# 1-Schematic_project_BIMO.net
KiCad netlist of a schematic drawn in EasyEDA
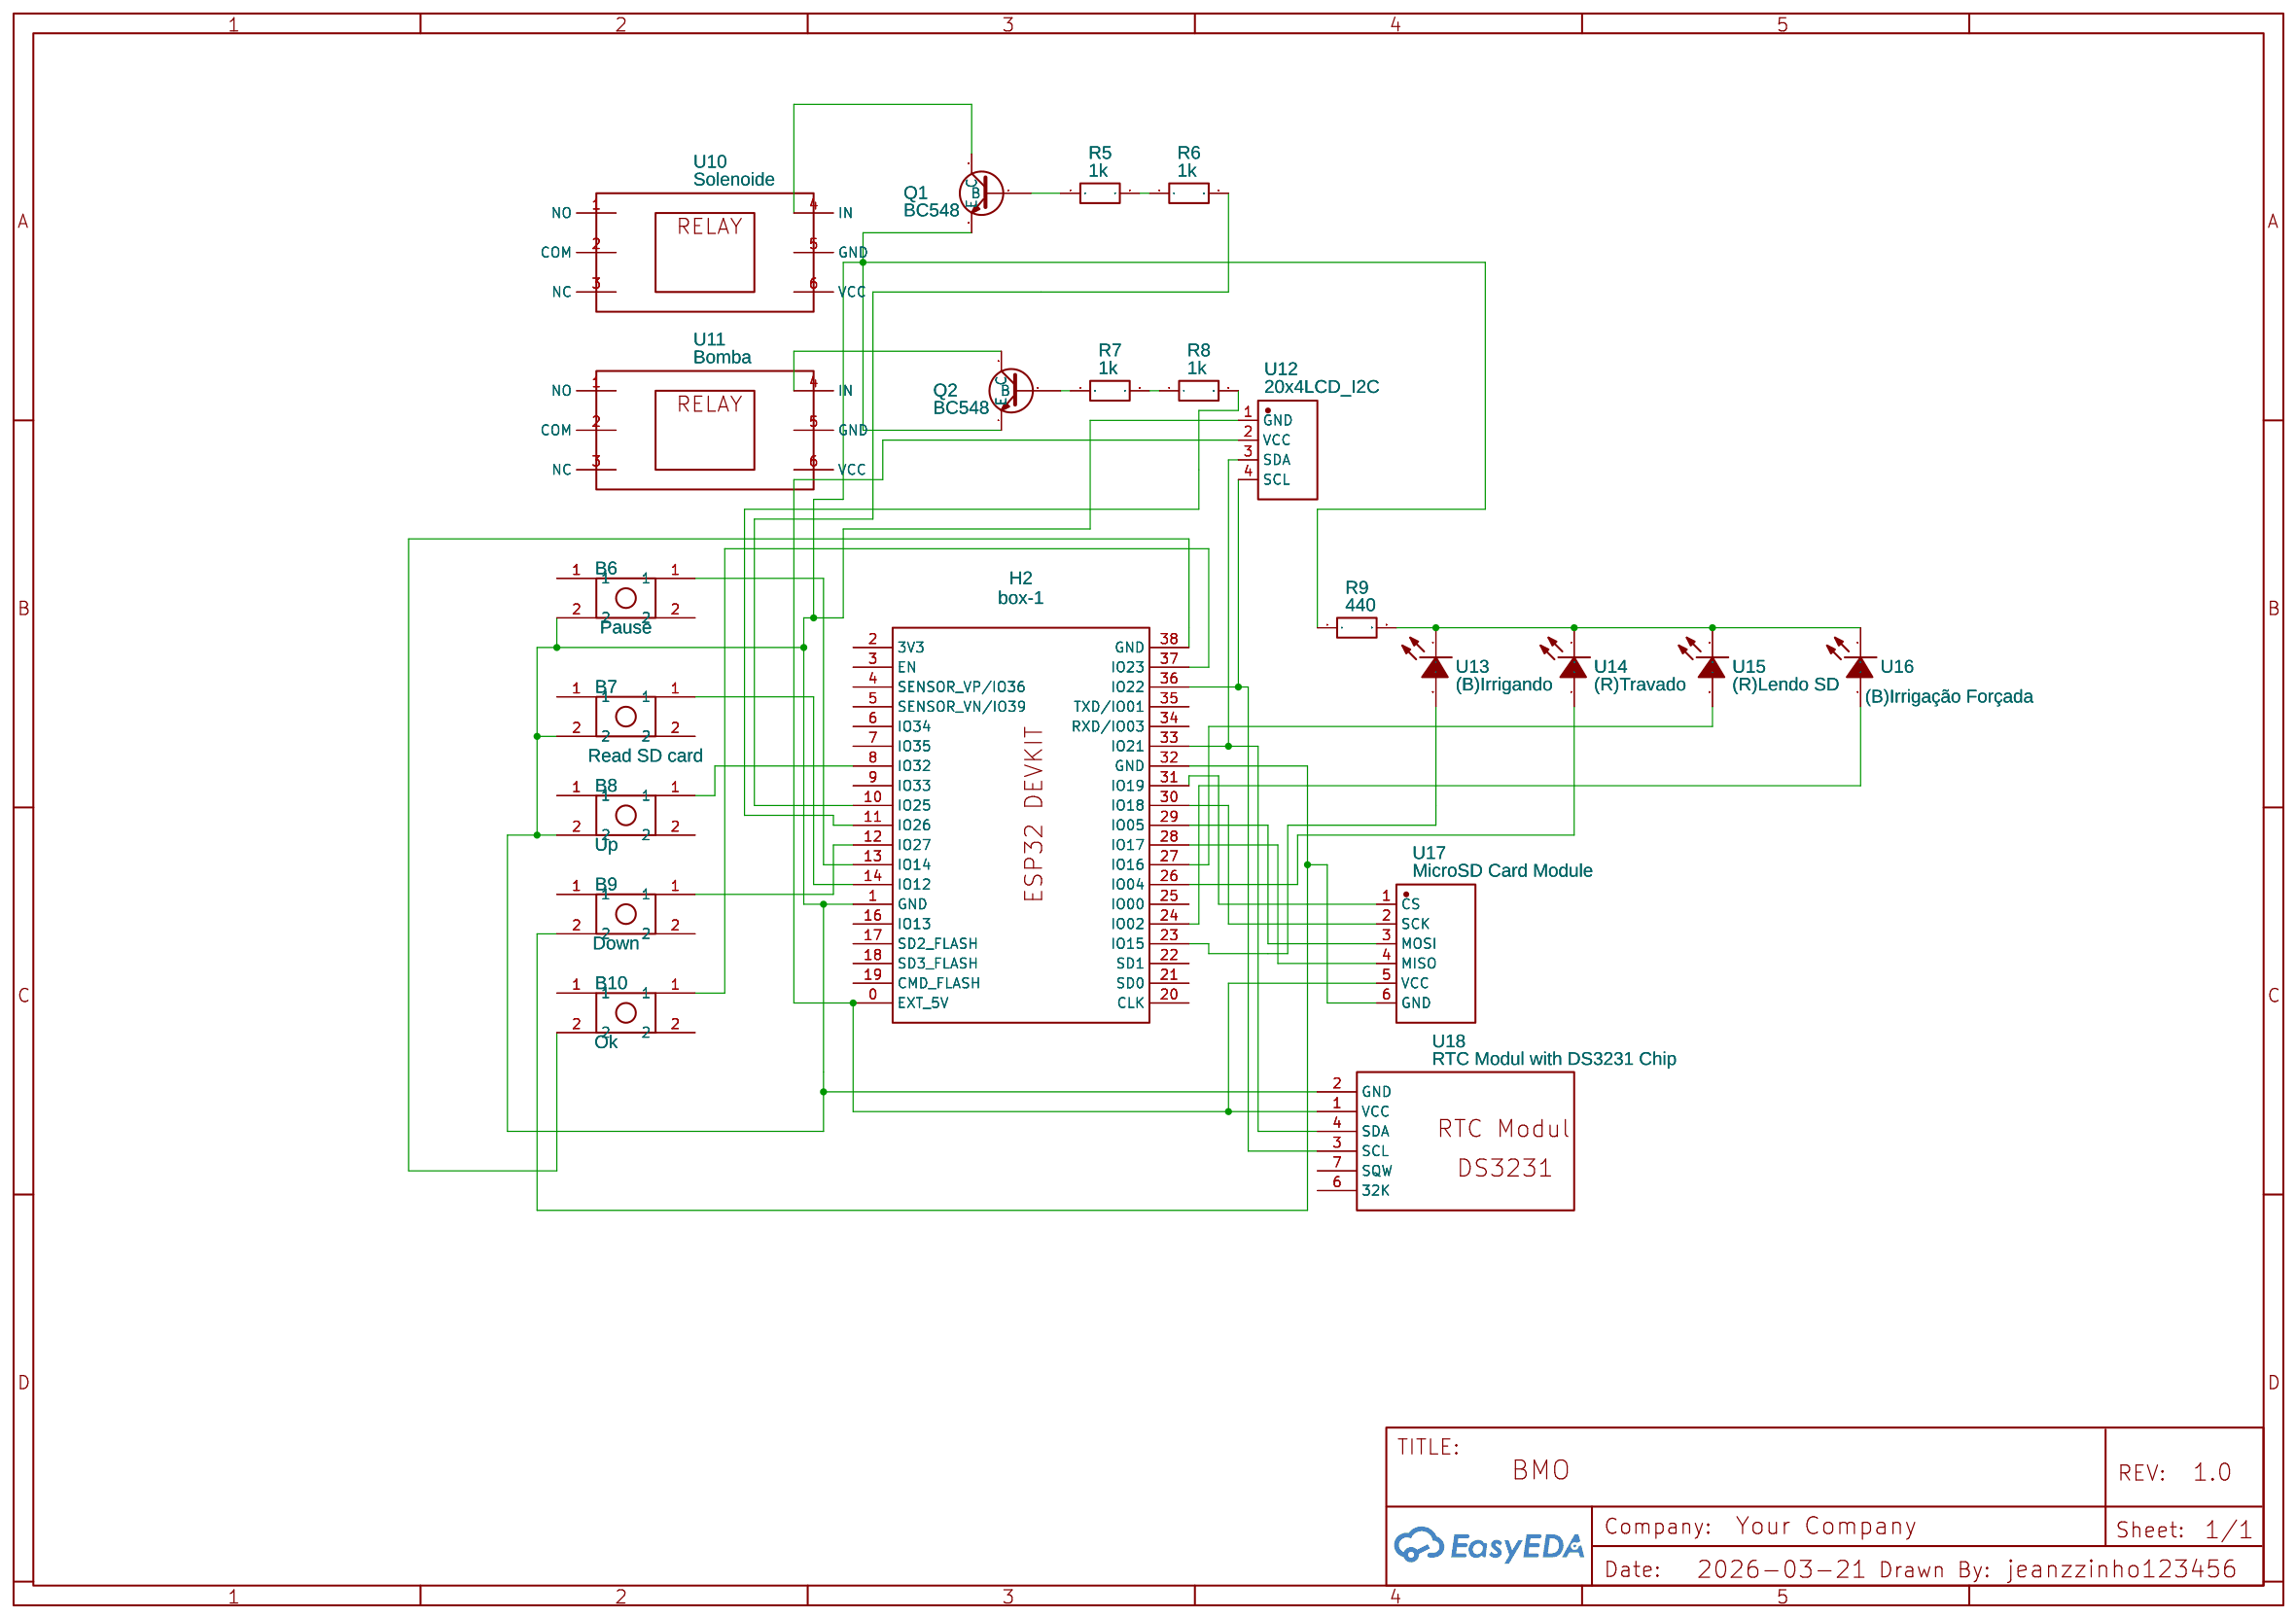
[diagram p0: schematic sheet]

(export (version "E")
  (design (tool "Eeschema 10.0.6"))
  (components
    (comp (ref "B6") (value "Pause") (libsource (lib "") (part "Push-buttom smd 6x6")))
    (comp (ref "B7") (value "Read SD card") (libsource (lib "") (part "Push-buttom smd 6x6")))
    (comp (ref "B8") (value "Up") (libsource (lib "") (part "Push-buttom smd 6x6")))
    (comp (ref "B9") (value "Down") (libsource (lib "") (part "Push-buttom smd 6x6")))
    (comp (ref "B10") (value "Ok") (libsource (lib "") (part "Push-buttom smd 6x6")))
    (comp (ref "H2")
      (value "box-1")
      (fields
        (field (name "Manufacturer Part") "2.54mm 1*19P Female header")
        (field (name "Manufacturer") "BOOMELE")
      )
      (libsource (lib "") (part "box-1"))
    )
    (comp (ref "Q1") (value "BC548") (libsource (lib "") (part "TRANSISTOR NPN CBE")))
    (comp (ref "Q2") (value "BC548") (libsource (lib "") (part "TRANSISTOR NPN CBE")))
    (comp (ref "R5") (value "1k") (libsource (lib "") (part "R_0603_EU")))
    (comp (ref "R6") (value "1k") (libsource (lib "") (part "R_0603_EU")))
    (comp (ref "R7") (value "1k") (libsource (lib "") (part "R_0603_EU")))
    (comp (ref "R8") (value "1k") (libsource (lib "") (part "R_0603_EU")))
    (comp (ref "R9") (value "440") (libsource (lib "") (part "R_0603_EU")))
    (comp (ref "U10") (value "Solenoide") (libsource (lib "") (part "1 CHANNEL RELAY MODULE")))
    (comp (ref "U11") (value "Bomba") (libsource (lib "") (part "1 CHANNEL RELAY MODULE")))
    (comp (ref "U12") (value "20x4LCD_I2C") (libsource (lib "") (part "20x4LCD_I2C")))
    (comp (ref "U13")
      (value "(B)Irrigando")
      (fields (field (name "Manufacturer Part") "720-LCGH9RNMXNX1"))
      (libsource (lib "") (part "720-LCGH9RNMXNX1"))
    )
    (comp (ref "U14")
      (value "(R)Travado")
      (fields (field (name "Manufacturer Part") "720-LCGH9RNMXNX1"))
      (libsource (lib "") (part "720-LCGH9RNMXNX1"))
    )
    (comp (ref "U15")
      (value "(R)Lendo SD")
      (fields (field (name "Manufacturer Part") "720-LCGH9RNMXNX1"))
      (libsource (lib "") (part "720-LCGH9RNMXNX1"))
    )
    (comp (ref "U16")
      (value "(B)Irrigação Forçada")
      (fields (field (name "Manufacturer Part") "720-LCGH9RNMXNX1"))
      (libsource (lib "") (part "720-LCGH9RNMXNX1"))
    )
    (comp (ref "U17") (value "MicroSD Card Module") (libsource (lib "") (part "MicroSD Card Module")))
    (comp (ref "U18")
      (value "RTC Modul with DS3231 Chip")
      (libsource (lib "") (part "RTC Modul with DS3231 Chip"))
    )
  )
  (nets
    (net (code "1") (name "Net-(B10-Pad2)_1") (class "Default")
      (node (ref "B10") (pin "2") (pinfunction "2_2") (pintype "input"))
      (node (ref "H2") (pin "38") (pinfunction "GND_38") (pintype "passive"))
    )
    (net (code "2") (name "Net-(H2-EXT_5V)") (class "Default")
      (node (ref "H2") (pin "0") (pinfunction "EXT_5V_0") (pintype "passive"))
      (node (ref "U12") (pin "2") (pinfunction "VCC_2") (pintype "unspecified"))
      (node (ref "U17") (pin "5") (pinfunction "VCC_5") (pintype "unspecified"))
      (node (ref "U18") (pin "1") (pinfunction "VCC_1") (pintype "unspecified"))
    )
    (net (code "3") (name "Net-(H2-IO02)") (class "Default")
      (node (ref "H2") (pin "23") (pinfunction "IO15_23") (pintype "bidirectional"))
      (node (ref "H2") (pin "24") (pinfunction "IO02_24") (pintype "bidirectional"))
      (node (ref "U13") (pin "2") (pinfunction "A_2") (pintype "unspecified"))
      (node (ref "U16") (pin "2") (pinfunction "A_2") (pintype "unspecified"))
    )
    (net (code "4") (name "Net-(H2-IO04)") (class "Default")
      (node (ref "H2") (pin "26") (pinfunction "IO04_26") (pintype "bidirectional"))
      (node (ref "U14") (pin "2") (pinfunction "A_2") (pintype "unspecified"))
    )
    (net (code "5") (name "Net-(H2-IO05)") (class "Default")
      (node (ref "H2") (pin "29") (pinfunction "IO05_29") (pintype "bidirectional"))
      (node (ref "U17") (pin "3") (pinfunction "MOSI_3") (pintype "unspecified"))
    )
    (net (code "6") (name "Net-(H2-IO12)") (class "Default")
      (node (ref "B7") (pin "1") (pinfunction "1_1") (pintype "output"))
      (node (ref "H2") (pin "14") (pinfunction "IO12_14") (pintype "bidirectional"))
    )
    (net (code "7") (name "Net-(H2-IO14)") (class "Default")
      (node (ref "B6") (pin "1") (pinfunction "1_1") (pintype "output"))
      (node (ref "H2") (pin "13") (pinfunction "IO14_13") (pintype "bidirectional"))
    )
    (net (code "8") (name "Net-(H2-IO16)") (class "Default")
      (node (ref "H2") (pin "27") (pinfunction "IO16_27") (pintype "bidirectional"))
      (node (ref "U15") (pin "2") (pinfunction "A_2") (pintype "unspecified"))
    )
    (net (code "9") (name "Net-(H2-IO17)") (class "Default")
      (node (ref "H2") (pin "28") (pinfunction "IO17_28") (pintype "bidirectional"))
      (node (ref "U17") (pin "4") (pinfunction "MISO_4") (pintype "unspecified"))
    )
    (net (code "10") (name "Net-(H2-IO18)") (class "Default")
      (node (ref "H2") (pin "30") (pinfunction "IO18_30") (pintype "bidirectional"))
      (node (ref "U17") (pin "2") (pinfunction "SCK_2") (pintype "unspecified"))
    )
    (net (code "11") (name "Net-(H2-IO19)") (class "Default")
      (node (ref "H2") (pin "31") (pinfunction "IO19_31") (pintype "bidirectional"))
      (node (ref "U17") (pin "1") (pinfunction "CS_1") (pintype "unspecified"))
    )
    (net (code "12") (name "Net-(H2-IO21)") (class "Default")
      (node (ref "H2") (pin "33") (pinfunction "IO21_33") (pintype "bidirectional"))
      (node (ref "U12") (pin "3") (pinfunction "SDA_3") (pintype "unspecified"))
      (node (ref "U18") (pin "4") (pinfunction "SDA_4") (pintype "unspecified"))
    )
    (net (code "13") (name "Net-(H2-IO22)") (class "Default")
      (node (ref "H2") (pin "36") (pinfunction "IO22_36") (pintype "bidirectional"))
      (node (ref "U12") (pin "4") (pinfunction "SCL_4") (pintype "unspecified"))
      (node (ref "U18") (pin "3") (pinfunction "SCL_3") (pintype "unspecified"))
    )
    (net (code "14") (name "Net-(H2-IO23)") (class "Default")
      (node (ref "B10") (pin "1") (pinfunction "1_1") (pintype "output"))
      (node (ref "H2") (pin "37") (pinfunction "IO23_37") (pintype "bidirectional"))
    )
    (net (code "15") (name "Net-(H2-IO25)") (class "Default")
      (node (ref "H2") (pin "10") (pinfunction "IO25_10") (pintype "bidirectional"))
      (node (ref "R6") (pin "2") (pinfunction "2_2") (pintype "unspecified"))
    )
    (net (code "16") (name "Net-(H2-IO26)") (class "Default")
      (node (ref "H2") (pin "11") (pinfunction "IO26_11") (pintype "bidirectional"))
      (node (ref "R8") (pin "2") (pinfunction "2_2") (pintype "unspecified"))
    )
    (net (code "17") (name "Net-(H2-IO27)") (class "Default")
      (node (ref "B9") (pin "1") (pinfunction "1_1") (pintype "output"))
      (node (ref "H2") (pin "12") (pinfunction "IO27_12") (pintype "bidirectional"))
    )
    (net (code "18") (name "Net-(H2-IO32)") (class "Default")
      (node (ref "B8") (pin "1") (pinfunction "1_1") (pintype "output"))
      (node (ref "H2") (pin "8") (pinfunction "IO32_8") (pintype "bidirectional"))
    )
    (net (code "19") (name "Net-(Q1-B)") (class "Default")
      (node (ref "Q1") (pin "2") (pinfunction "B_2") (pintype "input"))
      (node (ref "R5") (pin "1") (pinfunction "1_1") (pintype "unspecified"))
    )
    (net (code "20") (name "Net-(Q1-C)") (class "Default")
      (node (ref "Q1") (pin "3") (pinfunction "C_3") (pintype "unspecified"))
      (node (ref "U10") (pin "4") (pinfunction "IN_4") (pintype "unspecified"))
    )
    (net (code "21") (name "Net-(Q1-E)") (class "Default")
      (node (ref "B6") (pin "2") (pinfunction "2_2") (pintype "input"))
      (node (ref "B7") (pin "2") (pinfunction "2_2") (pintype "input"))
      (node (ref "B8") (pin "2") (pinfunction "2_2") (pintype "input"))
      (node (ref "H2") (pin "1") (pinfunction "GND_1") (pintype "passive"))
      (node (ref "Q1") (pin "1") (pinfunction "E_1") (pintype "unspecified"))
      (node (ref "Q2") (pin "1") (pinfunction "E_1") (pintype "unspecified"))
      (node (ref "R9") (pin "1") (pinfunction "1_1") (pintype "unspecified"))
      (node (ref "U12") (pin "1") (pinfunction "GND_1") (pintype "unspecified"))
      (node (ref "U18") (pin "2") (pinfunction "GND_2") (pintype "unspecified"))
    )
    (net (code "22") (name "Net-(Q2-B)") (class "Default")
      (node (ref "Q2") (pin "2") (pinfunction "B_2") (pintype "input"))
      (node (ref "R7") (pin "1") (pinfunction "1_1") (pintype "unspecified"))
    )
    (net (code "23") (name "Net-(Q2-C)") (class "Default")
      (node (ref "Q2") (pin "3") (pinfunction "C_3") (pintype "unspecified"))
      (node (ref "U11") (pin "4") (pinfunction "IN_4") (pintype "unspecified"))
    )
    (net (code "24") (name "Net-(R5-Pad2)") (class "Default")
      (node (ref "R5") (pin "2") (pinfunction "2_2") (pintype "unspecified"))
      (node (ref "R6") (pin "1") (pinfunction "1_1") (pintype "unspecified"))
    )
    (net (code "25") (name "Net-(R7-Pad2)") (class "Default")
      (node (ref "R7") (pin "2") (pinfunction "2_2") (pintype "unspecified"))
      (node (ref "R8") (pin "1") (pinfunction "1_1") (pintype "unspecified"))
    )
    (net (code "26") (name "Net-(U13-K)") (class "Default")
      (node (ref "R9") (pin "2") (pinfunction "2_2") (pintype "unspecified"))
      (node (ref "U13") (pin "1") (pinfunction "K_1") (pintype "unspecified"))
      (node (ref "U14") (pin "1") (pinfunction "K_1") (pintype "unspecified"))
      (node (ref "U15") (pin "1") (pinfunction "K_1") (pintype "unspecified"))
      (node (ref "U16") (pin "1") (pinfunction "K_1") (pintype "unspecified"))
    )
    (net (code "27") (name "Net-(U17-GND)") (class "Default")
      (node (ref "B9") (pin "2") (pinfunction "2_2") (pintype "input"))
      (node (ref "H2") (pin "32") (pinfunction "GND_32") (pintype "passive"))
      (node (ref "U17") (pin "6") (pinfunction "GND_6") (pintype "unspecified"))
    )
    (net (code "28") (name "unconnected-(B6-Pad1)") (class "Default")
      (node (ref "B6") (pin "1") (pinfunction "1_1") (pintype "input"))
    )
    (net (code "29") (name "unconnected-(B6-Pad2)") (class "Default")
      (node (ref "B6") (pin "2") (pinfunction "2_2") (pintype "output"))
    )
    (net (code "30") (name "unconnected-(B7-Pad1)") (class "Default")
      (node (ref "B7") (pin "1") (pinfunction "1_1") (pintype "input"))
    )
    (net (code "31") (name "unconnected-(B7-Pad2)") (class "Default")
      (node (ref "B7") (pin "2") (pinfunction "2_2") (pintype "output"))
    )
    (net (code "32") (name "unconnected-(B8-Pad1)") (class "Default")
      (node (ref "B8") (pin "1") (pinfunction "1_1") (pintype "input"))
    )
    (net (code "33") (name "unconnected-(B8-Pad2)") (class "Default")
      (node (ref "B8") (pin "2") (pinfunction "2_2") (pintype "output"))
    )
    (net (code "34") (name "unconnected-(B9-Pad1)") (class "Default")
      (node (ref "B9") (pin "1") (pinfunction "1_1") (pintype "input"))
    )
    (net (code "35") (name "unconnected-(B9-Pad2)") (class "Default")
      (node (ref "B9") (pin "2") (pinfunction "2_2") (pintype "output"))
    )
    (net (code "36") (name "unconnected-(B10-Pad1)") (class "Default")
      (node (ref "B10") (pin "1") (pinfunction "1_1") (pintype "input"))
    )
    (net (code "37") (name "unconnected-(B10-Pad2)") (class "Default")
      (node (ref "B10") (pin "2") (pinfunction "2_2") (pintype "output"))
    )
    (net (code "38") (name "unconnected-(H2-3V3-Pad2)") (class "Default")
      (node (ref "H2") (pin "2") (pinfunction "3V3_2") (pintype "passive"))
    )
    (net (code "39") (name "unconnected-(H2-CLK-Pad20)") (class "Default")
      (node (ref "H2") (pin "20") (pinfunction "CLK_20") (pintype "bidirectional"))
    )
    (net (code "40") (name "unconnected-(H2-CMD_FLASH-Pad19)") (class "Default")
      (node (ref "H2") (pin "19") (pinfunction "CMD_FLASH_19") (pintype "bidirectional"))
    )
    (net (code "41") (name "unconnected-(H2-EN-Pad3)") (class "Default")
      (node (ref "H2") (pin "3") (pinfunction "EN_3") (pintype "bidirectional"))
    )
    (net (code "42") (name "unconnected-(H2-IO00-Pad25)") (class "Default")
      (node (ref "H2") (pin "25") (pinfunction "IO00_25") (pintype "bidirectional"))
    )
    (net (code "43") (name "unconnected-(H2-IO13-Pad16)") (class "Default")
      (node (ref "H2") (pin "16") (pinfunction "IO13_16") (pintype "bidirectional"))
    )
    (net (code "44") (name "unconnected-(H2-IO33-Pad9)") (class "Default")
      (node (ref "H2") (pin "9") (pinfunction "IO33_9") (pintype "bidirectional"))
    )
    (net (code "45") (name "unconnected-(H2-IO34-Pad6)") (class "Default")
      (node (ref "H2") (pin "6") (pinfunction "IO34_6") (pintype "bidirectional"))
    )
    (net (code "46") (name "unconnected-(H2-IO35-Pad7)") (class "Default")
      (node (ref "H2") (pin "7") (pinfunction "IO35_7") (pintype "bidirectional"))
    )
    (net (code "47") (name "unconnected-(H2-RXD{slash}IO03-Pad34)") (class "Default")
      (node (ref "H2") (pin "34") (pinfunction "RXD/IO03_34") (pintype "bidirectional"))
    )
    (net (code "48") (name "unconnected-(H2-SD0-Pad21)") (class "Default")
      (node (ref "H2") (pin "21") (pinfunction "SD0_21") (pintype "bidirectional"))
    )
    (net (code "49") (name "unconnected-(H2-SD1-Pad22)") (class "Default")
      (node (ref "H2") (pin "22") (pinfunction "SD1_22") (pintype "bidirectional"))
    )
    (net (code "50") (name "unconnected-(H2-SD2_FLASH-Pad17)") (class "Default")
      (node (ref "H2") (pin "17") (pinfunction "SD2_FLASH_17") (pintype "bidirectional"))
    )
    (net (code "51") (name "unconnected-(H2-SD3_FLASH-Pad18)") (class "Default")
      (node (ref "H2") (pin "18") (pinfunction "SD3_FLASH_18") (pintype "bidirectional"))
    )
    (net (code "52") (name "unconnected-(H2-SENSOR_VN{slash}IO39-Pad5)") (class "Default")
      (node (ref "H2") (pin "5") (pinfunction "SENSOR_VN/IO39_5") (pintype "bidirectional"))
    )
    (net (code "53") (name "unconnected-(H2-SENSOR_VP{slash}IO36-Pad4)") (class "Default")
      (node (ref "H2") (pin "4") (pinfunction "SENSOR_VP/IO36_4") (pintype "bidirectional"))
    )
    (net (code "54") (name "unconnected-(H2-TXD{slash}IO01-Pad35)") (class "Default")
      (node (ref "H2") (pin "35") (pinfunction "TXD/IO01_35") (pintype "bidirectional"))
    )
    (net (code "55") (name "unconnected-(U10-COM-Pad2)") (class "Default")
      (node (ref "U10") (pin "2") (pinfunction "COM_2") (pintype "unspecified"))
    )
    (net (code "56") (name "unconnected-(U10-GND-Pad5)") (class "Default")
      (node (ref "U10") (pin "5") (pinfunction "GND_5") (pintype "unspecified"))
    )
    (net (code "57") (name "unconnected-(U10-NC-Pad3)") (class "Default")
      (node (ref "U10") (pin "3") (pinfunction "NC_3") (pintype "unspecified"))
    )
    (net (code "58") (name "unconnected-(U10-NO-Pad1)") (class "Default")
      (node (ref "U10") (pin "1") (pinfunction "NO_1") (pintype "unspecified"))
    )
    (net (code "59") (name "unconnected-(U10-VCC-Pad6)") (class "Default")
      (node (ref "U10") (pin "6") (pinfunction "VCC_6") (pintype "unspecified"))
    )
    (net (code "60") (name "unconnected-(U11-COM-Pad2)") (class "Default")
      (node (ref "U11") (pin "2") (pinfunction "COM_2") (pintype "unspecified"))
    )
    (net (code "61") (name "unconnected-(U11-GND-Pad5)") (class "Default")
      (node (ref "U11") (pin "5") (pinfunction "GND_5") (pintype "unspecified"))
    )
    (net (code "62") (name "unconnected-(U11-NC-Pad3)") (class "Default")
      (node (ref "U11") (pin "3") (pinfunction "NC_3") (pintype "unspecified"))
    )
    (net (code "63") (name "unconnected-(U11-NO-Pad1)") (class "Default")
      (node (ref "U11") (pin "1") (pinfunction "NO_1") (pintype "unspecified"))
    )
    (net (code "64") (name "unconnected-(U11-VCC-Pad6)") (class "Default")
      (node (ref "U11") (pin "6") (pinfunction "VCC_6") (pintype "unspecified"))
    )
    (net (code "65") (name "unconnected-(U18-32K-Pad6)") (class "Default")
      (node (ref "U18") (pin "6") (pinfunction "32K_6") (pintype "unspecified"))
    )
    (net (code "66") (name "unconnected-(U18-SQW-Pad7)") (class "Default")
      (node (ref "U18") (pin "7") (pinfunction "SQW_7") (pintype "unspecified"))
    )
  )
)
